# topologia_puente_con_rshunt.net
KiCad netlist of a schematic drawn in Altium Designer
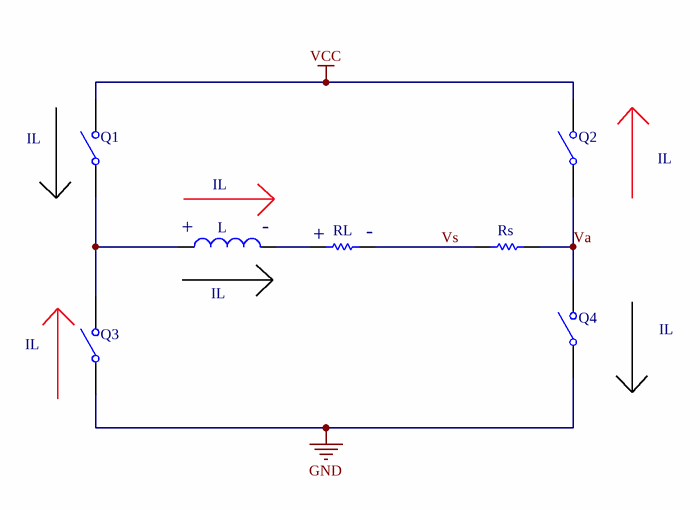
[diagram p0: topologia_puente_con_rshunt.SchDoc]

(export (version "E")
  (design (tool "Eeschema 10.0.6"))
  (components
    (comp (ref "L")
      (value "Inductor")
      (footprint "0402-A")
      (fields (field (name "PUBLISHER") "Altium Limited"))
      (libsource (lib "Miscellaneous Devices") (part "Inductor"))
    )
    (comp (ref "Q1")
      (value "SW-SPST")
      (footprint "SPST-2")
      (description "Single-Pole, Single-Throw Switch")
      (fields (field (name "PUBLISHER") "Altium Limited"))
      (libsource (lib "Miscellaneous Devices") (part "SW-SPST"))
    )
    (comp (ref "Q2")
      (value "SW-SPST")
      (footprint "SPST-2")
      (description "Single-Pole, Single-Throw Switch")
      (fields (field (name "PUBLISHER") "Altium Limited"))
      (libsource (lib "Miscellaneous Devices") (part "SW-SPST"))
    )
    (comp (ref "Q3")
      (value "SW-SPST")
      (footprint "SPST-2")
      (description "Single-Pole, Single-Throw Switch")
      (fields (field (name "PUBLISHER") "Altium Limited"))
      (libsource (lib "Miscellaneous Devices") (part "SW-SPST"))
    )
    (comp (ref "Q4")
      (value "SW-SPST")
      (footprint "SPST-2")
      (description "Single-Pole, Single-Throw Switch")
      (fields (field (name "PUBLISHER") "Altium Limited"))
      (libsource (lib "Miscellaneous Devices") (part "SW-SPST"))
    )
    (comp (ref "RL")
      (value "Res1")
      (footprint "AXIAL-0.3")
      (description "Resistor")
      (fields (field (name "PUBLISHER") "Altium Limited"))
      (libsource (lib "Miscellaneous Devices") (part "Res1"))
    )
    (comp (ref "Rs")
      (value "Res1")
      (footprint "AXIAL-0.3")
      (description "Resistor")
      (fields (field (name "PUBLISHER") "Altium Limited"))
      (libsource (lib "Miscellaneous Devices") (part "Res1"))
    )
  )
  (nets
    (net (code "1") (name "/Va") (class "Default")
      (node (ref "Q2") (pin "1") (pinfunction "COMMON_1") (pintype "passive"))
      (node (ref "Q4") (pin "2") (pinfunction "NO_2") (pintype "passive"))
      (node (ref "Rs") (pin "2") (pinfunction "2_2") (pintype "passive"))
    )
    (net (code "2") (name "/Vs") (class "Default")
      (node (ref "RL") (pin "2") (pinfunction "2_2") (pintype "passive"))
      (node (ref "Rs") (pin "1") (pinfunction "1_1") (pintype "passive"))
    )
    (net (code "3") (name "GND") (class "Default")
      (node (ref "Q3") (pin "1") (pinfunction "COMMON_1") (pintype "passive"))
      (node (ref "Q4") (pin "1") (pinfunction "COMMON_1") (pintype "passive"))
    )
    (net (code "4") (name "Net-(L-Pad2)") (class "Default")
      (node (ref "L") (pin "2") (pinfunction "2_2") (pintype "passive"))
      (node (ref "RL") (pin "1") (pinfunction "1_1") (pintype "passive"))
    )
    (net (code "5") (name "Net-(Q1-COMMON)") (class "Default")
      (node (ref "L") (pin "1") (pinfunction "1_1") (pintype "passive"))
      (node (ref "Q1") (pin "1") (pinfunction "COMMON_1") (pintype "passive"))
      (node (ref "Q3") (pin "2") (pinfunction "NO_2") (pintype "passive"))
    )
    (net (code "6") (name "VCC") (class "Default")
      (node (ref "Q1") (pin "2") (pinfunction "NO_2") (pintype "passive"))
      (node (ref "Q2") (pin "2") (pinfunction "NO_2") (pintype "passive"))
    )
  )
)
